# schematic.net
KiCad netlist of a schematic drawn in EasyEDA
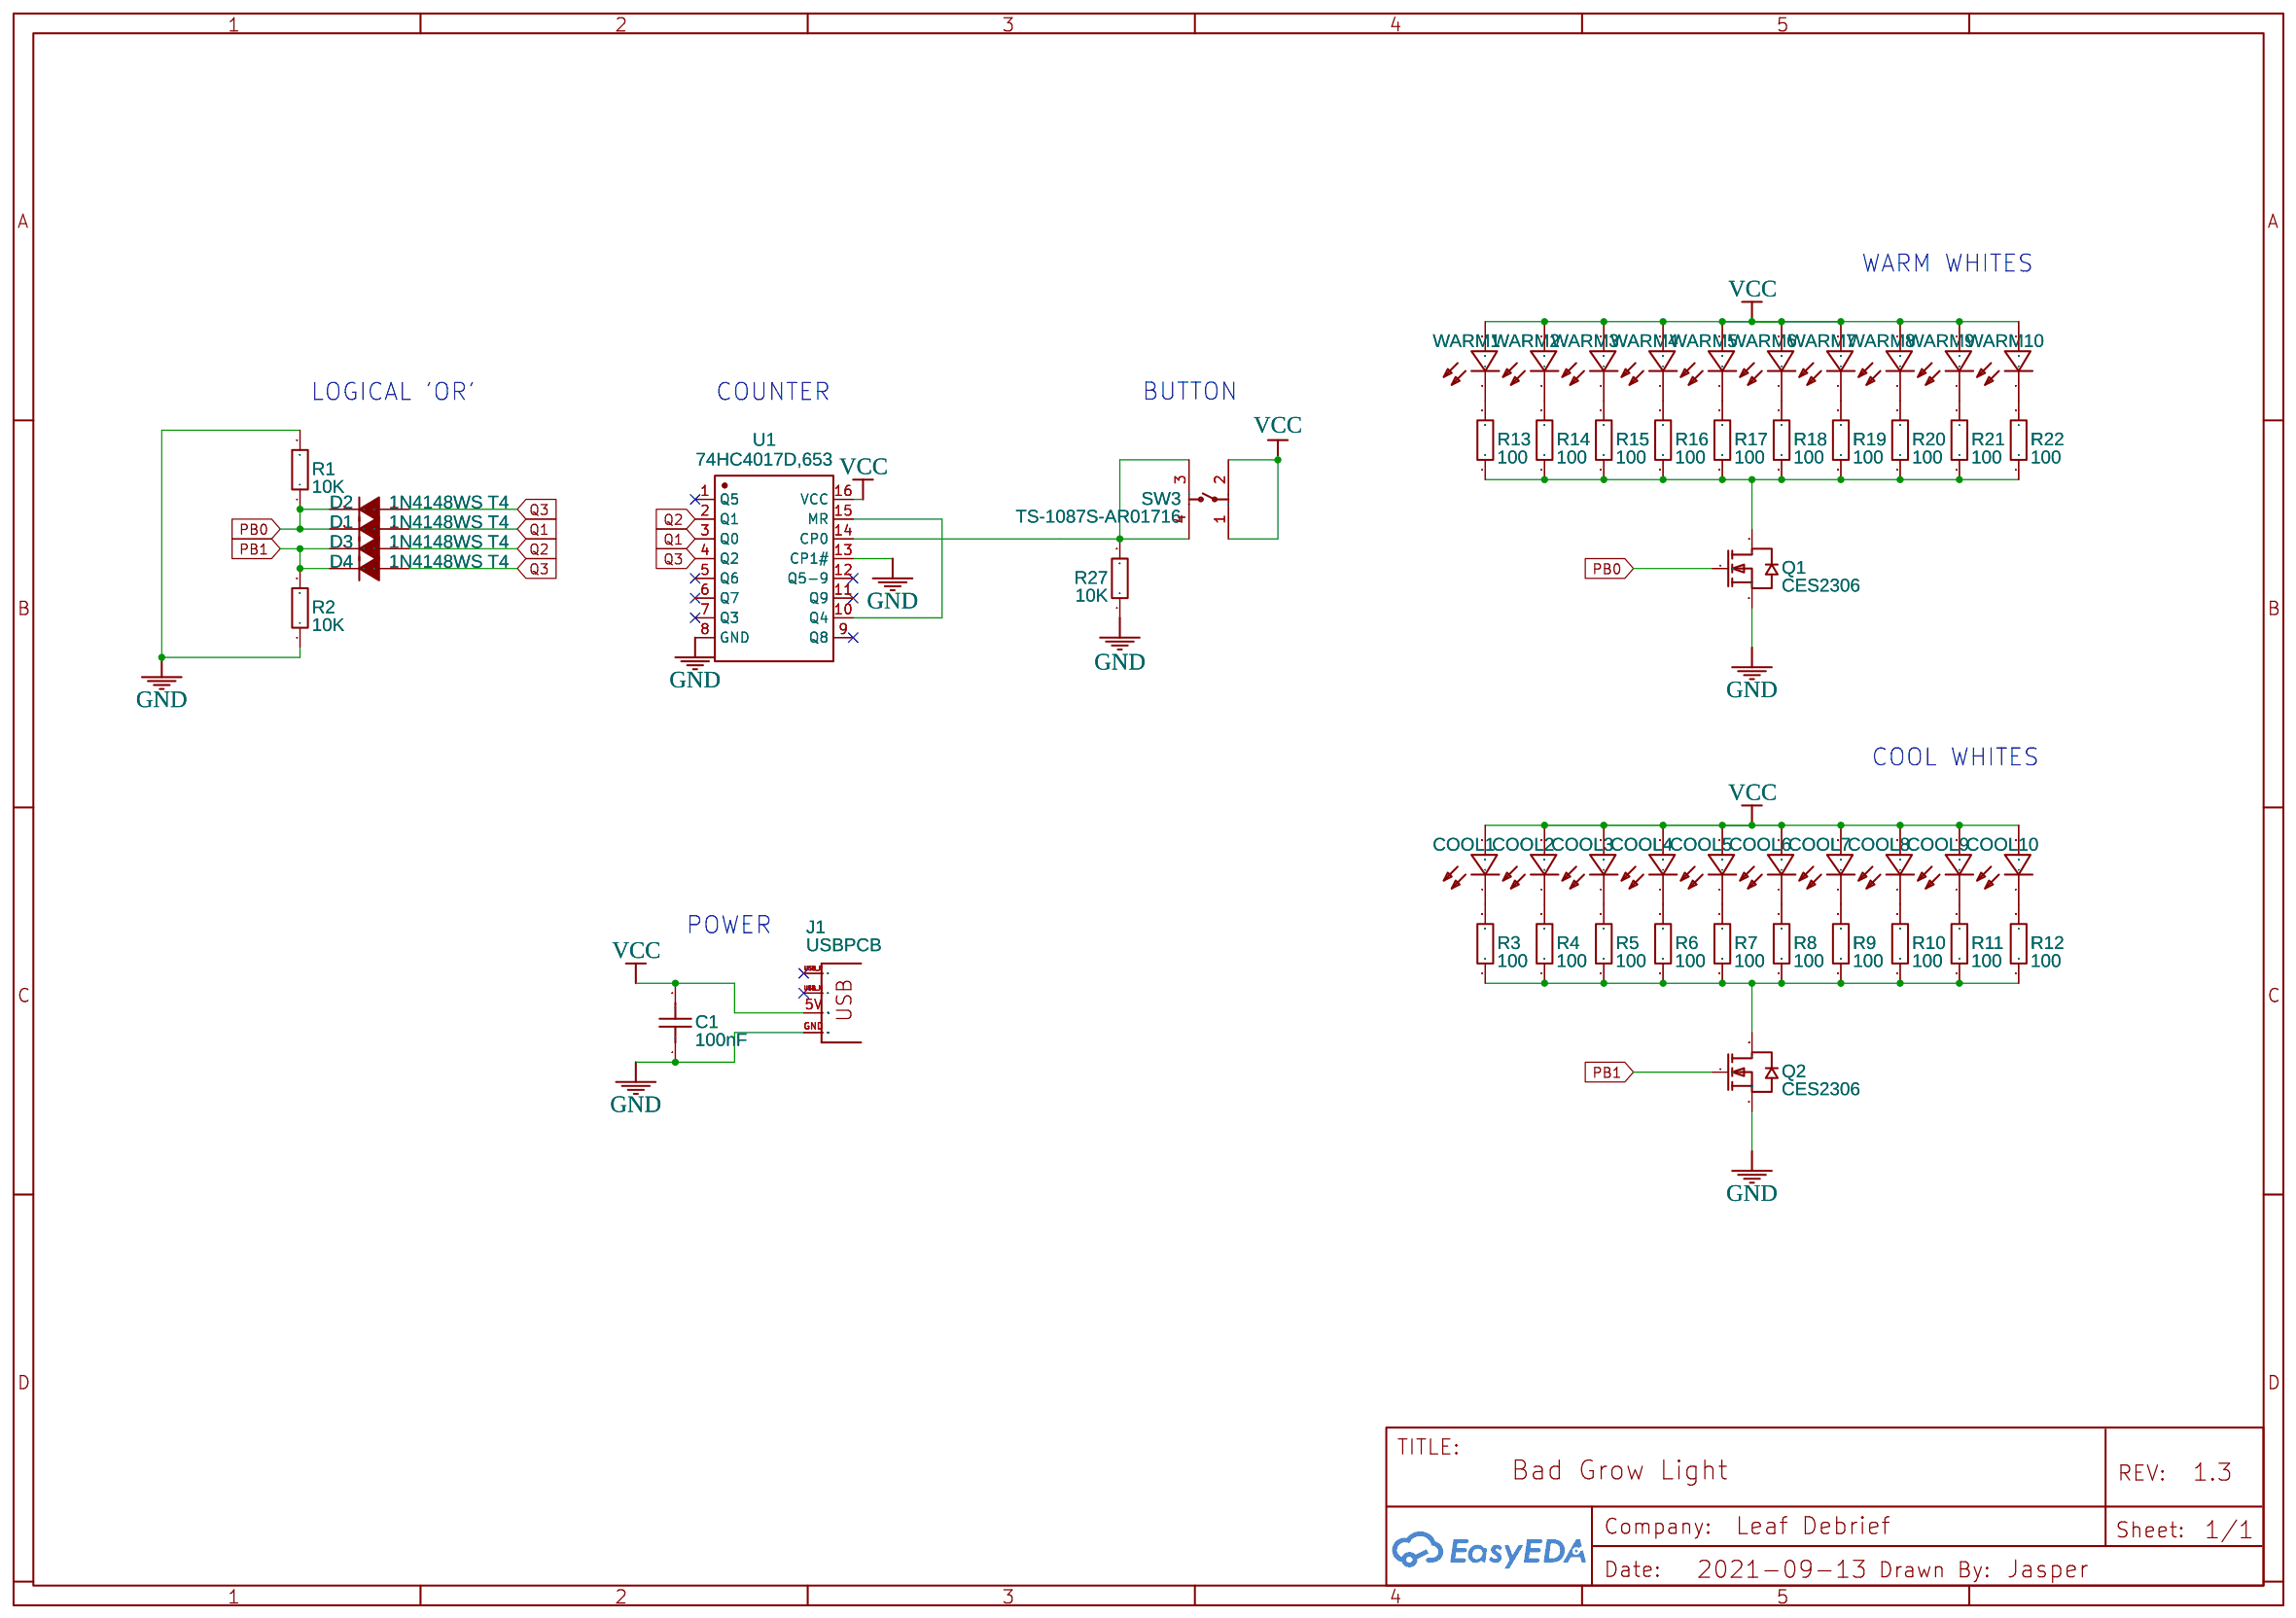
[diagram p0: schematic sheet]

(export (version "E")
  (design (tool "Eeschema 10.0.6"))
  (components
    (comp (ref "C1")
      (value "100nF")
      (fields
        (field (name "BOM_Manufacturer Part") "CC0603KRX7R9BB104")
        (field (name "BOM_Supplier Part") "C14663")
      )
      (libsource (lib "") (part "CC0603KRX7R9BB104"))
    )
    (comp (ref "COOL1")
      (value "HL-A-3014H416W-S1-08HL-HR3_C210338")
      (fields (field (name "BOM_Supplier Part") "C210338"))
      (libsource (lib "") (part "HL-A-3014H416W-S1-08HL-HR3_C210338"))
    )
    (comp (ref "COOL2")
      (value "HL-A-3014H416W-S1-08HL-HR3_C210338")
      (fields (field (name "BOM_Supplier Part") "C210338"))
      (libsource (lib "") (part "HL-A-3014H416W-S1-08HL-HR3_C210338"))
    )
    (comp (ref "COOL3")
      (value "HL-A-3014H416W-S1-08HL-HR3_C210338")
      (fields (field (name "BOM_Supplier Part") "C210338"))
      (libsource (lib "") (part "HL-A-3014H416W-S1-08HL-HR3_C210338"))
    )
    (comp (ref "COOL4")
      (value "HL-A-3014H416W-S1-08HL-HR3_C210338")
      (fields (field (name "BOM_Supplier Part") "C210338"))
      (libsource (lib "") (part "HL-A-3014H416W-S1-08HL-HR3_C210338"))
    )
    (comp (ref "COOL5")
      (value "HL-A-3014H416W-S1-08HL-HR3_C210338")
      (fields (field (name "BOM_Supplier Part") "C210338"))
      (libsource (lib "") (part "HL-A-3014H416W-S1-08HL-HR3_C210338"))
    )
    (comp (ref "COOL6")
      (value "HL-A-3014H416W-S1-08HL-HR3_C210338")
      (fields (field (name "BOM_Supplier Part") "C210338"))
      (libsource (lib "") (part "HL-A-3014H416W-S1-08HL-HR3_C210338"))
    )
    (comp (ref "COOL7")
      (value "HL-A-3014H416W-S1-08HL-HR3_C210338")
      (fields (field (name "BOM_Supplier Part") "C210338"))
      (libsource (lib "") (part "HL-A-3014H416W-S1-08HL-HR3_C210338"))
    )
    (comp (ref "COOL8")
      (value "HL-A-3014H416W-S1-08HL-HR3_C210338")
      (fields (field (name "BOM_Supplier Part") "C210338"))
      (libsource (lib "") (part "HL-A-3014H416W-S1-08HL-HR3_C210338"))
    )
    (comp (ref "COOL9")
      (value "HL-A-3014H416W-S1-08HL-HR3_C210338")
      (fields (field (name "BOM_Supplier Part") "C210338"))
      (libsource (lib "") (part "HL-A-3014H416W-S1-08HL-HR3_C210338"))
    )
    (comp (ref "COOL10")
      (value "HL-A-3014H416W-S1-08HL-HR3_C210338")
      (fields (field (name "BOM_Supplier Part") "C210338"))
      (libsource (lib "") (part "HL-A-3014H416W-S1-08HL-HR3_C210338"))
    )
    (comp (ref "D1")
      (value "1N4148WS T4")
      (fields (field (name "BOM_Supplier Part") "C2128"))
      (libsource (lib "") (part "1N4148WS T4"))
    )
    (comp (ref "D2")
      (value "1N4148WS T4")
      (fields (field (name "BOM_Supplier Part") "C2128"))
      (libsource (lib "") (part "1N4148WS T4"))
    )
    (comp (ref "D3")
      (value "1N4148WS T4")
      (fields (field (name "BOM_Supplier Part") "C2128"))
      (libsource (lib "") (part "1N4148WS T4"))
    )
    (comp (ref "D4")
      (value "1N4148WS T4")
      (fields (field (name "BOM_Supplier Part") "C2128"))
      (libsource (lib "") (part "1N4148WS T4"))
    )
    (comp (ref "J1") (value "USBPCB") (libsource (lib "") (part "USBPCB")))
    (comp (ref "Q1")
      (value "CES2306")
      (fields (field (name "BOM_Supplier Part") "C154290"))
      (libsource (lib "") (part "CES2306"))
    )
    (comp (ref "Q2")
      (value "CES2306")
      (fields (field (name "BOM_Supplier Part") "C154290"))
      (libsource (lib "") (part "CES2306"))
    )
    (comp (ref "R1")
      (value "10K")
      (fields
        (field (name "BOM_Manufacturer Part") "AC0603FR-0710KL")
        (field (name "BOM_Supplier Part") "C116677")
      )
      (libsource (lib "") (part "AC0603FR-0710KL"))
    )
    (comp (ref "R2")
      (value "10K")
      (fields
        (field (name "BOM_Manufacturer Part") "AC0603FR-0710KL")
        (field (name "BOM_Supplier Part") "C116677")
      )
      (libsource (lib "") (part "AC0603FR-0710KL"))
    )
    (comp (ref "R3")
      (value "100")
      (fields
        (field (name "BOM_Manufacturer Part") "0603WAJ0101T5E")
        (field (name "BOM_Supplier Part") "C25201")
      )
      (libsource (lib "") (part "0603WAJ0101T5E"))
    )
    (comp (ref "R4")
      (value "100")
      (fields
        (field (name "BOM_Manufacturer Part") "0603WAJ0101T5E")
        (field (name "BOM_Supplier Part") "C25201")
      )
      (libsource (lib "") (part "0603WAJ0101T5E"))
    )
    (comp (ref "R5")
      (value "100")
      (fields
        (field (name "BOM_Manufacturer Part") "0603WAJ0101T5E")
        (field (name "BOM_Supplier Part") "C25201")
      )
      (libsource (lib "") (part "0603WAJ0101T5E"))
    )
    (comp (ref "R6")
      (value "100")
      (fields
        (field (name "BOM_Manufacturer Part") "0603WAJ0101T5E")
        (field (name "BOM_Supplier Part") "C25201")
      )
      (libsource (lib "") (part "0603WAJ0101T5E"))
    )
    (comp (ref "R7")
      (value "100")
      (fields
        (field (name "BOM_Manufacturer Part") "0603WAJ0101T5E")
        (field (name "BOM_Supplier Part") "C25201")
      )
      (libsource (lib "") (part "0603WAJ0101T5E"))
    )
    (comp (ref "R8")
      (value "100")
      (fields
        (field (name "BOM_Manufacturer Part") "0603WAJ0101T5E")
        (field (name "BOM_Supplier Part") "C25201")
      )
      (libsource (lib "") (part "0603WAJ0101T5E"))
    )
    (comp (ref "R9")
      (value "100")
      (fields
        (field (name "BOM_Manufacturer Part") "0603WAJ0101T5E")
        (field (name "BOM_Supplier Part") "C25201")
      )
      (libsource (lib "") (part "0603WAJ0101T5E"))
    )
    (comp (ref "R10")
      (value "100")
      (fields
        (field (name "BOM_Manufacturer Part") "0603WAJ0101T5E")
        (field (name "BOM_Supplier Part") "C25201")
      )
      (libsource (lib "") (part "0603WAJ0101T5E"))
    )
    (comp (ref "R11")
      (value "100")
      (fields
        (field (name "BOM_Manufacturer Part") "0603WAJ0101T5E")
        (field (name "BOM_Supplier Part") "C25201")
      )
      (libsource (lib "") (part "0603WAJ0101T5E"))
    )
    (comp (ref "R12")
      (value "100")
      (fields
        (field (name "BOM_Manufacturer Part") "0603WAJ0101T5E")
        (field (name "BOM_Supplier Part") "C25201")
      )
      (libsource (lib "") (part "0603WAJ0101T5E"))
    )
    (comp (ref "R13")
      (value "100")
      (fields
        (field (name "BOM_Manufacturer Part") "0603WAJ0101T5E")
        (field (name "BOM_Supplier Part") "C25201")
      )
      (libsource (lib "") (part "0603WAJ0101T5E"))
    )
    (comp (ref "R14")
      (value "100")
      (fields
        (field (name "BOM_Manufacturer Part") "0603WAJ0101T5E")
        (field (name "BOM_Supplier Part") "C25201")
      )
      (libsource (lib "") (part "0603WAJ0101T5E"))
    )
    (comp (ref "R15")
      (value "100")
      (fields
        (field (name "BOM_Manufacturer Part") "0603WAJ0101T5E")
        (field (name "BOM_Supplier Part") "C25201")
      )
      (libsource (lib "") (part "0603WAJ0101T5E"))
    )
    (comp (ref "R16")
      (value "100")
      (fields
        (field (name "BOM_Manufacturer Part") "0603WAJ0101T5E")
        (field (name "BOM_Supplier Part") "C25201")
      )
      (libsource (lib "") (part "0603WAJ0101T5E"))
    )
    (comp (ref "R17")
      (value "100")
      (fields
        (field (name "BOM_Manufacturer Part") "0603WAJ0101T5E")
        (field (name "BOM_Supplier Part") "C25201")
      )
      (libsource (lib "") (part "0603WAJ0101T5E"))
    )
    (comp (ref "R18")
      (value "100")
      (fields
        (field (name "BOM_Manufacturer Part") "0603WAJ0101T5E")
        (field (name "BOM_Supplier Part") "C25201")
      )
      (libsource (lib "") (part "0603WAJ0101T5E"))
    )
    (comp (ref "R19")
      (value "100")
      (fields
        (field (name "BOM_Manufacturer Part") "0603WAJ0101T5E")
        (field (name "BOM_Supplier Part") "C25201")
      )
      (libsource (lib "") (part "0603WAJ0101T5E"))
    )
    (comp (ref "R20")
      (value "100")
      (fields
        (field (name "BOM_Manufacturer Part") "0603WAJ0101T5E")
        (field (name "BOM_Supplier Part") "C25201")
      )
      (libsource (lib "") (part "0603WAJ0101T5E"))
    )
    (comp (ref "R21")
      (value "100")
      (fields
        (field (name "BOM_Manufacturer Part") "0603WAJ0101T5E")
        (field (name "BOM_Supplier Part") "C25201")
      )
      (libsource (lib "") (part "0603WAJ0101T5E"))
    )
    (comp (ref "R22")
      (value "100")
      (fields
        (field (name "BOM_Manufacturer Part") "0603WAJ0101T5E")
        (field (name "BOM_Supplier Part") "C25201")
      )
      (libsource (lib "") (part "0603WAJ0101T5E"))
    )
    (comp (ref "R27")
      (value "10K")
      (fields
        (field (name "BOM_Manufacturer Part") "AC0603FR-0710KL")
        (field (name "BOM_Supplier Part") "C116677")
      )
      (libsource (lib "") (part "AC0603FR-0710KL"))
    )
    (comp (ref "SW3")
      (value "TS-1087S-AR01716")
      (fields (field (name "BOM_Supplier Part") "C720466"))
      (libsource (lib "") (part "TS-1087S-AR01716"))
    )
    (comp (ref "U1")
      (value "74HC4017D,653")
      (fields (field (name "BOM_Supplier Part") "C148206"))
      (libsource (lib "") (part "74HC4017D,653"))
    )
    (comp (ref "WARM1")
      (value "HL-A-3014H416W-S1-08HL-HR3_C210338")
      (fields (field (name "BOM_Supplier Part") "C210338"))
      (libsource (lib "") (part "HL-A-3014H416W-S1-08HL-HR3_C210338_1"))
    )
    (comp (ref "WARM2")
      (value "HL-A-3014H416W-S1-08HL-HR3_C210338")
      (fields (field (name "BOM_Supplier Part") "C210338"))
      (libsource (lib "") (part "HL-A-3014H416W-S1-08HL-HR3_C210338_1"))
    )
    (comp (ref "WARM3")
      (value "HL-A-3014H416W-S1-08HL-HR3_C210338")
      (fields (field (name "BOM_Supplier Part") "C210338"))
      (libsource (lib "") (part "HL-A-3014H416W-S1-08HL-HR3_C210338_1"))
    )
    (comp (ref "WARM4")
      (value "HL-A-3014H416W-S1-08HL-HR3_C210338")
      (fields (field (name "BOM_Supplier Part") "C210338"))
      (libsource (lib "") (part "HL-A-3014H416W-S1-08HL-HR3_C210338_1"))
    )
    (comp (ref "WARM5")
      (value "HL-A-3014H416W-S1-08HL-HR3_C210338")
      (fields (field (name "BOM_Supplier Part") "C210338"))
      (libsource (lib "") (part "HL-A-3014H416W-S1-08HL-HR3_C210338_1"))
    )
    (comp (ref "WARM6")
      (value "HL-A-3014H416W-S1-08HL-HR3_C210338")
      (fields (field (name "BOM_Supplier Part") "C210338"))
      (libsource (lib "") (part "HL-A-3014H416W-S1-08HL-HR3_C210338_1"))
    )
    (comp (ref "WARM7")
      (value "HL-A-3014H416W-S1-08HL-HR3_C210338")
      (fields (field (name "BOM_Supplier Part") "C210338"))
      (libsource (lib "") (part "HL-A-3014H416W-S1-08HL-HR3_C210338_1"))
    )
    (comp (ref "WARM8")
      (value "HL-A-3014H416W-S1-08HL-HR3_C210338")
      (fields (field (name "BOM_Supplier Part") "C210338"))
      (libsource (lib "") (part "HL-A-3014H416W-S1-08HL-HR3_C210338_1"))
    )
    (comp (ref "WARM9")
      (value "HL-A-3014H416W-S1-08HL-HR3_C210338")
      (fields (field (name "BOM_Supplier Part") "C210338"))
      (libsource (lib "") (part "HL-A-3014H416W-S1-08HL-HR3_C210338_1"))
    )
    (comp (ref "WARM10")
      (value "HL-A-3014H416W-S1-08HL-HR3_C210338")
      (fields (field (name "BOM_Supplier Part") "C210338"))
      (libsource (lib "") (part "HL-A-3014H416W-S1-08HL-HR3_C210338_1"))
    )
  )
  (nets
    (net (code "1") (name "GND") (class "Default")
      (node (ref "C1") (pin "1") (pinfunction "1_1") (pintype "unspecified"))
      (node (ref "J1") (pin "GND") (pinfunction "GND_GND") (pintype "bidirectional"))
      (node (ref "Q1") (pin "2") (pinfunction "S_2") (pintype "unspecified"))
      (node (ref "Q2") (pin "2") (pinfunction "S_2") (pintype "unspecified"))
      (node (ref "R1") (pin "2") (pinfunction "2_2") (pintype "input"))
      (node (ref "R2") (pin "1") (pinfunction "1_1") (pintype "input"))
      (node (ref "R27") (pin "1") (pinfunction "1_1") (pintype "input"))
      (node (ref "U1") (pin "13") (pinfunction "CP1#_13") (pintype "unspecified"))
      (node (ref "U1") (pin "8") (pinfunction "GND_8") (pintype "unspecified"))
    )
    (net (code "2") (name "Net-(COOL1-Pad1)") (class "Default")
      (node (ref "COOL1") (pin "1") (pinfunction "1_1") (pintype "unspecified"))
      (node (ref "R3") (pin "2") (pinfunction "2_2") (pintype "input"))
    )
    (net (code "3") (name "Net-(COOL2-Pad1)") (class "Default")
      (node (ref "COOL2") (pin "1") (pinfunction "1_1") (pintype "unspecified"))
      (node (ref "R4") (pin "2") (pinfunction "2_2") (pintype "input"))
    )
    (net (code "4") (name "Net-(COOL3-Pad1)") (class "Default")
      (node (ref "COOL3") (pin "1") (pinfunction "1_1") (pintype "unspecified"))
      (node (ref "R5") (pin "2") (pinfunction "2_2") (pintype "input"))
    )
    (net (code "5") (name "Net-(COOL4-Pad1)") (class "Default")
      (node (ref "COOL4") (pin "1") (pinfunction "1_1") (pintype "unspecified"))
      (node (ref "R6") (pin "2") (pinfunction "2_2") (pintype "input"))
    )
    (net (code "6") (name "Net-(COOL5-Pad1)") (class "Default")
      (node (ref "COOL5") (pin "1") (pinfunction "1_1") (pintype "unspecified"))
      (node (ref "R7") (pin "2") (pinfunction "2_2") (pintype "input"))
    )
    (net (code "7") (name "Net-(COOL6-Pad1)") (class "Default")
      (node (ref "COOL6") (pin "1") (pinfunction "1_1") (pintype "unspecified"))
      (node (ref "R8") (pin "2") (pinfunction "2_2") (pintype "input"))
    )
    (net (code "8") (name "Net-(COOL7-Pad1)") (class "Default")
      (node (ref "COOL7") (pin "1") (pinfunction "1_1") (pintype "unspecified"))
      (node (ref "R9") (pin "2") (pinfunction "2_2") (pintype "input"))
    )
    (net (code "9") (name "Net-(COOL8-Pad1)") (class "Default")
      (node (ref "COOL8") (pin "1") (pinfunction "1_1") (pintype "unspecified"))
      (node (ref "R10") (pin "2") (pinfunction "2_2") (pintype "input"))
    )
    (net (code "10") (name "Net-(COOL9-Pad1)") (class "Default")
      (node (ref "COOL9") (pin "1") (pinfunction "1_1") (pintype "unspecified"))
      (node (ref "R11") (pin "2") (pinfunction "2_2") (pintype "input"))
    )
    (net (code "11") (name "Net-(COOL10-Pad1)") (class "Default")
      (node (ref "COOL10") (pin "1") (pinfunction "1_1") (pintype "unspecified"))
      (node (ref "R12") (pin "2") (pinfunction "2_2") (pintype "input"))
    )
    (net (code "12") (name "Net-(Q1-D)") (class "Default")
      (node (ref "Q1") (pin "3") (pinfunction "D_3") (pintype "unspecified"))
      (node (ref "R13") (pin "1") (pinfunction "1_1") (pintype "input"))
      (node (ref "R14") (pin "1") (pinfunction "1_1") (pintype "input"))
      (node (ref "R15") (pin "1") (pinfunction "1_1") (pintype "input"))
      (node (ref "R16") (pin "1") (pinfunction "1_1") (pintype "input"))
      (node (ref "R17") (pin "1") (pinfunction "1_1") (pintype "input"))
      (node (ref "R18") (pin "1") (pinfunction "1_1") (pintype "input"))
      (node (ref "R19") (pin "1") (pinfunction "1_1") (pintype "input"))
      (node (ref "R20") (pin "1") (pinfunction "1_1") (pintype "input"))
      (node (ref "R21") (pin "1") (pinfunction "1_1") (pintype "input"))
      (node (ref "R22") (pin "1") (pinfunction "1_1") (pintype "input"))
    )
    (net (code "13") (name "Net-(Q2-D)") (class "Default")
      (node (ref "Q2") (pin "3") (pinfunction "D_3") (pintype "unspecified"))
      (node (ref "R10") (pin "1") (pinfunction "1_1") (pintype "input"))
      (node (ref "R11") (pin "1") (pinfunction "1_1") (pintype "input"))
      (node (ref "R12") (pin "1") (pinfunction "1_1") (pintype "input"))
      (node (ref "R3") (pin "1") (pinfunction "1_1") (pintype "input"))
      (node (ref "R4") (pin "1") (pinfunction "1_1") (pintype "input"))
      (node (ref "R5") (pin "1") (pinfunction "1_1") (pintype "input"))
      (node (ref "R6") (pin "1") (pinfunction "1_1") (pintype "input"))
      (node (ref "R7") (pin "1") (pinfunction "1_1") (pintype "input"))
      (node (ref "R8") (pin "1") (pinfunction "1_1") (pintype "input"))
      (node (ref "R9") (pin "1") (pinfunction "1_1") (pintype "input"))
    )
    (net (code "14") (name "Net-(R13-Pad2)") (class "Default")
      (node (ref "R13") (pin "2") (pinfunction "2_2") (pintype "input"))
      (node (ref "WARM1") (pin "1") (pinfunction "1_1") (pintype "unspecified"))
    )
    (net (code "15") (name "Net-(R14-Pad2)") (class "Default")
      (node (ref "R14") (pin "2") (pinfunction "2_2") (pintype "input"))
      (node (ref "WARM2") (pin "1") (pinfunction "1_1") (pintype "unspecified"))
    )
    (net (code "16") (name "Net-(R15-Pad2)") (class "Default")
      (node (ref "R15") (pin "2") (pinfunction "2_2") (pintype "input"))
      (node (ref "WARM3") (pin "1") (pinfunction "1_1") (pintype "unspecified"))
    )
    (net (code "17") (name "Net-(R16-Pad2)") (class "Default")
      (node (ref "R16") (pin "2") (pinfunction "2_2") (pintype "input"))
      (node (ref "WARM4") (pin "1") (pinfunction "1_1") (pintype "unspecified"))
    )
    (net (code "18") (name "Net-(R17-Pad2)") (class "Default")
      (node (ref "R17") (pin "2") (pinfunction "2_2") (pintype "input"))
      (node (ref "WARM5") (pin "1") (pinfunction "1_1") (pintype "unspecified"))
    )
    (net (code "19") (name "Net-(R18-Pad2)") (class "Default")
      (node (ref "R18") (pin "2") (pinfunction "2_2") (pintype "input"))
      (node (ref "WARM6") (pin "1") (pinfunction "1_1") (pintype "unspecified"))
    )
    (net (code "20") (name "Net-(R19-Pad2)") (class "Default")
      (node (ref "R19") (pin "2") (pinfunction "2_2") (pintype "input"))
      (node (ref "WARM7") (pin "1") (pinfunction "1_1") (pintype "unspecified"))
    )
    (net (code "21") (name "Net-(R20-Pad2)") (class "Default")
      (node (ref "R20") (pin "2") (pinfunction "2_2") (pintype "input"))
      (node (ref "WARM8") (pin "1") (pinfunction "1_1") (pintype "unspecified"))
    )
    (net (code "22") (name "Net-(R21-Pad2)") (class "Default")
      (node (ref "R21") (pin "2") (pinfunction "2_2") (pintype "input"))
      (node (ref "WARM9") (pin "1") (pinfunction "1_1") (pintype "unspecified"))
    )
    (net (code "23") (name "Net-(R22-Pad2)") (class "Default")
      (node (ref "R22") (pin "2") (pinfunction "2_2") (pintype "input"))
      (node (ref "WARM10") (pin "1") (pinfunction "1_1") (pintype "unspecified"))
    )
    (net (code "24") (name "Net-(U1-CP0)") (class "Default")
      (node (ref "R27") (pin "2") (pinfunction "2_2") (pintype "input"))
      (node (ref "SW3") (pin "3") (pinfunction "3_3") (pintype "unspecified"))
      (node (ref "SW3") (pin "4") (pinfunction "4_4") (pintype "unspecified"))
      (node (ref "U1") (pin "14") (pinfunction "CP0_14") (pintype "unspecified"))
    )
    (net (code "25") (name "Net-(U1-MR)") (class "Default")
      (node (ref "U1") (pin "10") (pinfunction "Q4_10") (pintype "unspecified"))
      (node (ref "U1") (pin "15") (pinfunction "MR_15") (pintype "unspecified"))
    )
    (net (code "26") (name "PB0") (class "Default")
      (node (ref "D1") (pin "1") (pinfunction "K_1") (pintype "unspecified"))
      (node (ref "D2") (pin "1") (pinfunction "K_1") (pintype "unspecified"))
      (node (ref "Q1") (pin "1") (pinfunction "G_1") (pintype "unspecified"))
      (node (ref "R1") (pin "1") (pinfunction "1_1") (pintype "input"))
    )
    (net (code "27") (name "PB1") (class "Default")
      (node (ref "D3") (pin "1") (pinfunction "K_1") (pintype "unspecified"))
      (node (ref "D4") (pin "1") (pinfunction "K_1") (pintype "unspecified"))
      (node (ref "Q2") (pin "1") (pinfunction "G_1") (pintype "unspecified"))
      (node (ref "R2") (pin "2") (pinfunction "2_2") (pintype "input"))
    )
    (net (code "28") (name "Q1") (class "Default")
      (node (ref "D1") (pin "2") (pinfunction "A_2") (pintype "unspecified"))
      (node (ref "U1") (pin "3") (pinfunction "Q0_3") (pintype "unspecified"))
    )
    (net (code "29") (name "Q2") (class "Default")
      (node (ref "D3") (pin "2") (pinfunction "A_2") (pintype "unspecified"))
      (node (ref "U1") (pin "2") (pinfunction "Q1_2") (pintype "unspecified"))
    )
    (net (code "30") (name "Q3") (class "Default")
      (node (ref "D2") (pin "2") (pinfunction "A_2") (pintype "unspecified"))
      (node (ref "D4") (pin "2") (pinfunction "A_2") (pintype "unspecified"))
      (node (ref "U1") (pin "4") (pinfunction "Q2_4") (pintype "unspecified"))
    )
    (net (code "31") (name "VCC") (class "Default")
      (node (ref "C1") (pin "2") (pinfunction "2_2") (pintype "unspecified"))
      (node (ref "COOL1") (pin "2") (pinfunction "2_2") (pintype "unspecified"))
      (node (ref "COOL10") (pin "2") (pinfunction "2_2") (pintype "unspecified"))
      (node (ref "COOL2") (pin "2") (pinfunction "2_2") (pintype "unspecified"))
      (node (ref "COOL3") (pin "2") (pinfunction "2_2") (pintype "unspecified"))
      (node (ref "COOL4") (pin "2") (pinfunction "2_2") (pintype "unspecified"))
      (node (ref "COOL5") (pin "2") (pinfunction "2_2") (pintype "unspecified"))
      (node (ref "COOL6") (pin "2") (pinfunction "2_2") (pintype "unspecified"))
      (node (ref "COOL7") (pin "2") (pinfunction "2_2") (pintype "unspecified"))
      (node (ref "COOL8") (pin "2") (pinfunction "2_2") (pintype "unspecified"))
      (node (ref "COOL9") (pin "2") (pinfunction "2_2") (pintype "unspecified"))
      (node (ref "J1") (pin "5V") (pinfunction "VBUS_5V") (pintype "bidirectional"))
      (node (ref "SW3") (pin "1") (pinfunction "1_1") (pintype "unspecified"))
      (node (ref "SW3") (pin "2") (pinfunction "2_2") (pintype "unspecified"))
      (node (ref "U1") (pin "16") (pinfunction "VCC_16") (pintype "unspecified"))
      (node (ref "WARM1") (pin "2") (pinfunction "2_2") (pintype "unspecified"))
      (node (ref "WARM10") (pin "2") (pinfunction "2_2") (pintype "unspecified"))
      (node (ref "WARM2") (pin "2") (pinfunction "2_2") (pintype "unspecified"))
      (node (ref "WARM3") (pin "2") (pinfunction "2_2") (pintype "unspecified"))
      (node (ref "WARM4") (pin "2") (pinfunction "2_2") (pintype "unspecified"))
      (node (ref "WARM5") (pin "2") (pinfunction "2_2") (pintype "unspecified"))
      (node (ref "WARM6") (pin "2") (pinfunction "2_2") (pintype "unspecified"))
      (node (ref "WARM7") (pin "2") (pinfunction "2_2") (pintype "unspecified"))
      (node (ref "WARM8") (pin "2") (pinfunction "2_2") (pintype "unspecified"))
      (node (ref "WARM9") (pin "2") (pinfunction "2_2") (pintype "unspecified"))
    )
    (net (code "32") (name "unconnected-(J1-D+-PadUSB_P)") (class "Default")
      (node (ref "J1") (pin "USB_P") (pinfunction "D+_USB_P") (pintype "bidirectional+no_connect"))
    )
    (net (code "33") (name "unconnected-(J1-D--PadUSB_M)") (class "Default")
      (node (ref "J1") (pin "USB_M") (pinfunction "D-_USB_M") (pintype "bidirectional+no_connect"))
    )
    (net (code "34") (name "unconnected-(U1-Q3-Pad7)") (class "Default")
      (node (ref "U1") (pin "7") (pinfunction "Q3_7") (pintype "unspecified+no_connect"))
    )
    (net (code "35") (name "unconnected-(U1-Q5-9-Pad12)") (class "Default")
      (node (ref "U1") (pin "12") (pinfunction "Q5-9_12") (pintype "unspecified+no_connect"))
    )
    (net (code "36") (name "unconnected-(U1-Q5-Pad1)") (class "Default")
      (node (ref "U1") (pin "1") (pinfunction "Q5_1") (pintype "unspecified+no_connect"))
    )
    (net (code "37") (name "unconnected-(U1-Q6-Pad5)") (class "Default")
      (node (ref "U1") (pin "5") (pinfunction "Q6_5") (pintype "unspecified+no_connect"))
    )
    (net (code "38") (name "unconnected-(U1-Q7-Pad6)") (class "Default")
      (node (ref "U1") (pin "6") (pinfunction "Q7_6") (pintype "unspecified+no_connect"))
    )
    (net (code "39") (name "unconnected-(U1-Q8-Pad9)") (class "Default")
      (node (ref "U1") (pin "9") (pinfunction "Q8_9") (pintype "unspecified+no_connect"))
    )
    (net (code "40") (name "unconnected-(U1-Q9-Pad11)") (class "Default")
      (node (ref "U1") (pin "11") (pinfunction "Q9_11") (pintype "unspecified+no_connect"))
    )
  )
)
